# layout.net
KiCad netlist of a schematic drawn in EAGLE
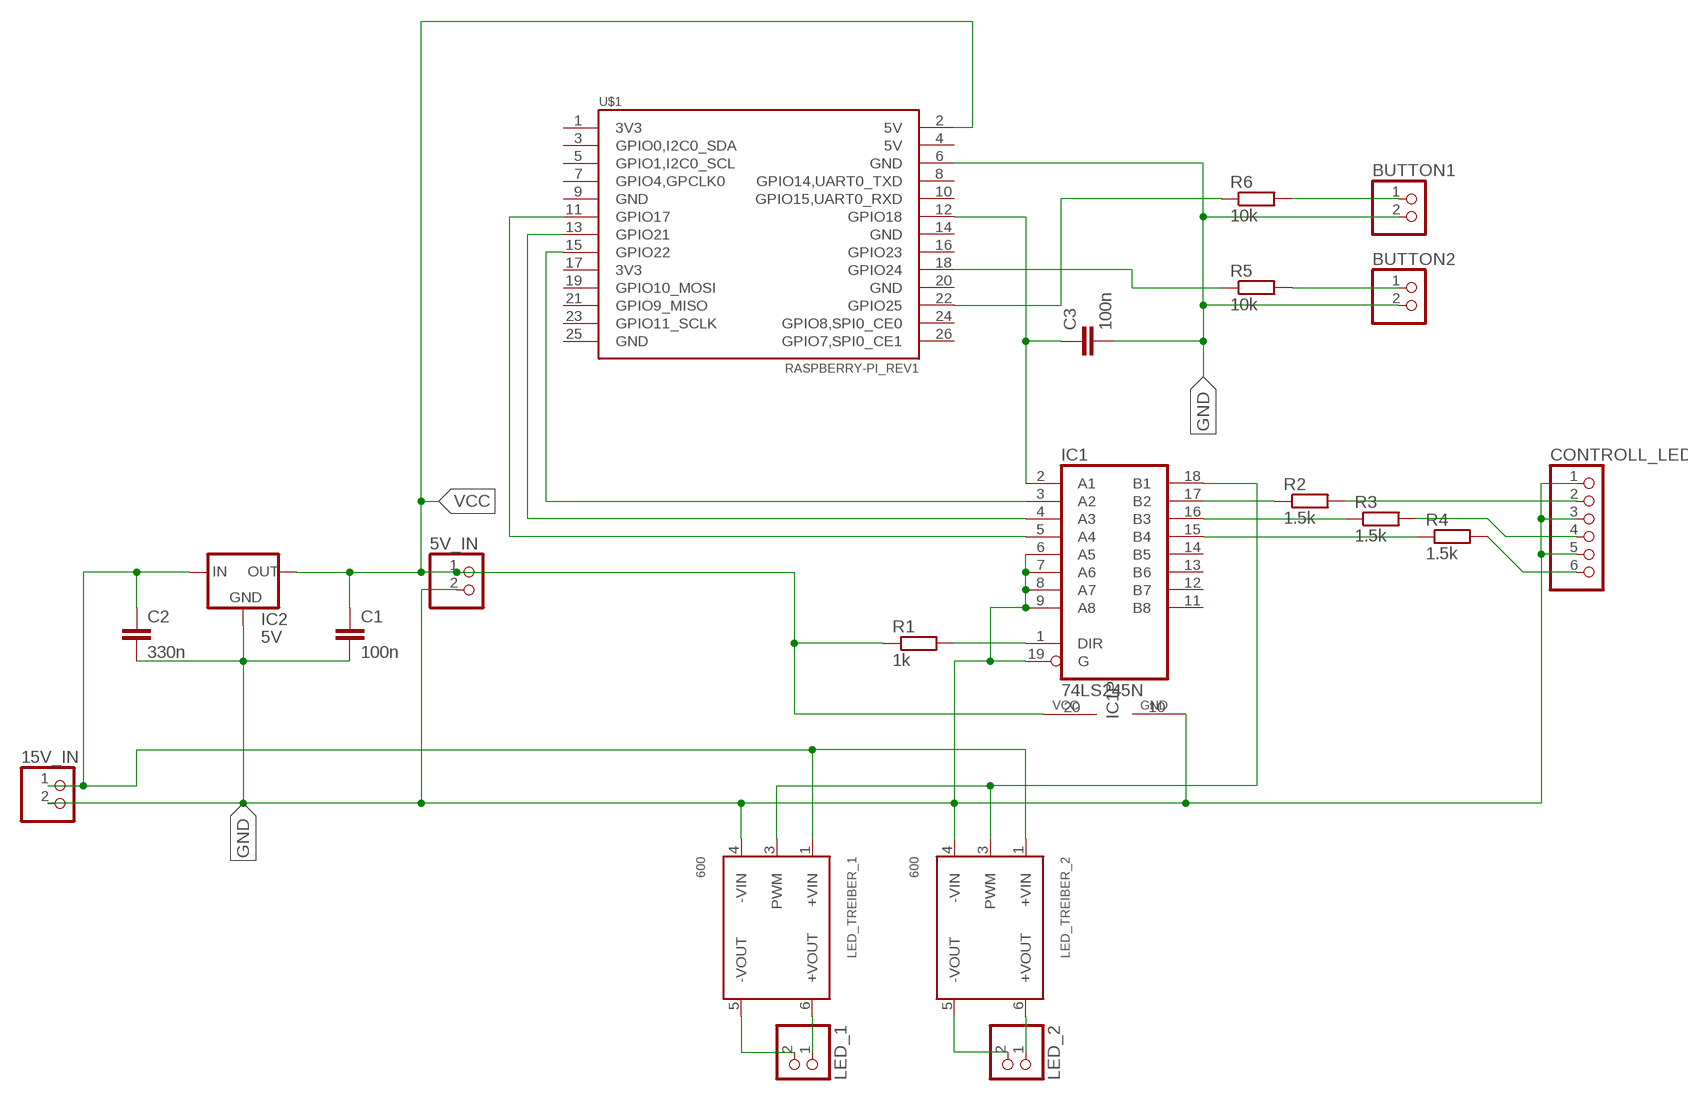
[diagram p0: schematic, sheet 1]

(export (version "E")
  (design (tool "Eeschema 10.0.6"))
  (components
    (comp (ref "5V_IN")
      (value "PINHD-1X2")
      (footprint "eagle-import:1X02")
      (libsource (lib "eagle-import") (part "PINHD-1X2"))
    )
    (comp (ref "15V_IN")
      (value "PINHD-1X2")
      (footprint "eagle-import:1X02")
      (libsource (lib "eagle-import") (part "PINHD-1X2"))
    )
    (comp (ref "BUTTON1")
      (value "PINHD-1X2")
      (footprint "eagle-import:1X02")
      (libsource (lib "eagle-import") (part "PINHD-1X2"))
    )
    (comp (ref "BUTTON2")
      (value "PINHD-1X2")
      (footprint "eagle-import:1X02")
      (libsource (lib "eagle-import") (part "PINHD-1X2"))
    )
    (comp (ref "C1")
      (value "100n")
      (footprint "eagle-import:C7.5B3")
      (libsource (lib "eagle-import") (part "C7.5/3"))
    )
    (comp (ref "C2")
      (value "330n")
      (footprint "eagle-import:C7.5B5")
      (libsource (lib "eagle-import") (part "C7.5/5"))
    )
    (comp (ref "C3")
      (value "100n")
      (footprint "eagle-import:C7.5B3")
      (libsource (lib "eagle-import") (part "C7.5/3"))
    )
    (comp (ref "CONTROLL_LED")
      (value "PINHD-1X6")
      (footprint "eagle-import:1X06")
      (libsource (lib "eagle-import") (part "PINHD-1X6"))
    )
    (comp (ref "IC1")
      (value "74LS245N")
      (footprint "eagle-import:DIL20")
      (libsource (lib "eagle-import") (part "74245NLS"))
    )
    (comp (ref "IC2")
      (value "5V")
      (footprint "eagle-import:78XXS")
      (libsource (lib "eagle-import") (part "78XXS"))
    )
    (comp (ref "LED_1")
      (value "PINHD-1X2")
      (footprint "eagle-import:1X02")
      (libsource (lib "eagle-import") (part "PINHD-1X2"))
    )
    (comp (ref "LED_2")
      (value "PINHD-1X2")
      (footprint "eagle-import:1X02")
      (libsource (lib "eagle-import") (part "PINHD-1X2"))
    )
    (comp (ref "LED_TREIBER_1")
      (value "600")
      (footprint "eagle-import:LDD-L1")
      (libsource (lib "eagle-import") (part "LDD-L1"))
    )
    (comp (ref "LED_TREIBER_2")
      (value "600")
      (footprint "eagle-import:LDD-L1")
      (libsource (lib "eagle-import") (part "LDD-L1"))
    )
    (comp (ref "R1")
      (value "1k")
      (footprint "eagle-import:0309_10")
      (libsource (lib "eagle-import") (part "R-EU_0309/10"))
    )
    (comp (ref "R2")
      (value "1.5k")
      (footprint "eagle-import:0309_10")
      (libsource (lib "eagle-import") (part "R-EU_0309/10"))
    )
    (comp (ref "R3")
      (value "1.5k")
      (footprint "eagle-import:0309_10")
      (libsource (lib "eagle-import") (part "R-EU_0309/10"))
    )
    (comp (ref "R4")
      (value "1.5k")
      (footprint "eagle-import:0309_10")
      (libsource (lib "eagle-import") (part "R-EU_0309/10"))
    )
    (comp (ref "R5")
      (value "10k")
      (footprint "eagle-import:0309_10")
      (libsource (lib "eagle-import") (part "R-EU_0309/10"))
    )
    (comp (ref "R6")
      (value "10k")
      (footprint "eagle-import:0309_10")
      (libsource (lib "eagle-import") (part "R-EU_0309/10"))
    )
    (comp (ref "U$1")
      (value "RASPBERRY-PI_REV1")
      (footprint "eagle-import:RASPBERRY-PI_REV1")
      (libsource (lib "eagle-import") (part "RASPBERRY-PI_REV1"))
    )
  )
  (nets
    (net (code "1") (name "GND") (class "Default")
      (node (ref "15V_IN") (pin "2") (pinfunction "2_2") (pintype "passive"))
      (node (ref "5V_IN") (pin "2") (pinfunction "2_2") (pintype "passive"))
      (node (ref "BUTTON1") (pin "2") (pinfunction "2_2") (pintype "passive"))
      (node (ref "BUTTON2") (pin "2") (pinfunction "2_2") (pintype "passive"))
      (node (ref "C1") (pin "2") (pinfunction "2_2") (pintype "passive"))
      (node (ref "C2") (pin "2") (pinfunction "2_2") (pintype "passive"))
      (node (ref "C3") (pin "2") (pinfunction "2_2") (pintype "passive"))
      (node (ref "CONTROLL_LED") (pin "1") (pinfunction "1_1") (pintype "passive"))
      (node (ref "CONTROLL_LED") (pin "3") (pinfunction "3_3") (pintype "passive"))
      (node (ref "CONTROLL_LED") (pin "5") (pinfunction "5_5") (pintype "passive"))
      (node (ref "IC1") (pin "10") (pinfunction "GND_10") (pintype "power_in"))
      (node (ref "IC1") (pin "19") (pinfunction "G_19") (pintype "input"))
      (node (ref "IC1") (pin "6") (pinfunction "A5_6") (pintype "bidirectional"))
      (node (ref "IC1") (pin "7") (pinfunction "A6_7") (pintype "bidirectional"))
      (node (ref "IC1") (pin "8") (pinfunction "A7_8") (pintype "bidirectional"))
      (node (ref "IC1") (pin "9") (pinfunction "A8_9") (pintype "bidirectional"))
      (node (ref "IC2") (pin "GND") (pinfunction "GND_GND") (pintype "input"))
      (node (ref "LED_TREIBER_1") (pin "4") (pinfunction "-VIN_4") (pintype "input"))
      (node (ref "LED_TREIBER_2") (pin "4") (pinfunction "-VIN_4") (pintype "input"))
      (node (ref "U$1") (pin "6") (pinfunction "GND_6") (pintype "bidirectional"))
    )
    (net (code "2") (name "Net-(BUTTON1-Pad1)") (class "Default")
      (node (ref "BUTTON1") (pin "1") (pinfunction "1_1") (pintype "passive"))
      (node (ref "R6") (pin "2") (pinfunction "2_2") (pintype "passive"))
    )
    (net (code "3") (name "Net-(BUTTON2-Pad1)") (class "Default")
      (node (ref "BUTTON2") (pin "1") (pinfunction "1_1") (pintype "passive"))
      (node (ref "R5") (pin "2") (pinfunction "2_2") (pintype "passive"))
    )
    (net (code "4") (name "Net-(CONTROLL_LED-Pad2)") (class "Default")
      (node (ref "CONTROLL_LED") (pin "2") (pinfunction "2_2") (pintype "passive"))
      (node (ref "R2") (pin "2") (pinfunction "2_2") (pintype "passive"))
    )
    (net (code "5") (name "Net-(CONTROLL_LED-Pad4)") (class "Default")
      (node (ref "CONTROLL_LED") (pin "4") (pinfunction "4_4") (pintype "passive"))
      (node (ref "R3") (pin "2") (pinfunction "2_2") (pintype "passive"))
    )
    (net (code "6") (name "Net-(CONTROLL_LED-Pad6)") (class "Default")
      (node (ref "CONTROLL_LED") (pin "6") (pinfunction "6_6") (pintype "passive"))
      (node (ref "R4") (pin "2") (pinfunction "2_2") (pintype "passive"))
    )
    (net (code "7") (name "Net-(IC1A-A1)") (class "Default")
      (node (ref "C3") (pin "1") (pinfunction "1_1") (pintype "passive"))
      (node (ref "IC1") (pin "2") (pinfunction "A1_2") (pintype "bidirectional"))
      (node (ref "U$1") (pin "12") (pinfunction "GPIO18_12") (pintype "bidirectional"))
    )
    (net (code "8") (name "Net-(IC1A-A2)") (class "Default")
      (node (ref "IC1") (pin "3") (pinfunction "A2_3") (pintype "bidirectional"))
      (node (ref "U$1") (pin "15") (pinfunction "GPIO22_15") (pintype "bidirectional"))
    )
    (net (code "9") (name "Net-(IC1A-A3)") (class "Default")
      (node (ref "IC1") (pin "4") (pinfunction "A3_4") (pintype "bidirectional"))
      (node (ref "U$1") (pin "13") (pinfunction "GPIO21_13") (pintype "bidirectional"))
    )
    (net (code "10") (name "Net-(IC1A-A4)") (class "Default")
      (node (ref "IC1") (pin "5") (pinfunction "A4_5") (pintype "bidirectional"))
      (node (ref "U$1") (pin "11") (pinfunction "GPIO17_11") (pintype "bidirectional"))
    )
    (net (code "11") (name "Net-(IC1A-B1)") (class "Default")
      (node (ref "IC1") (pin "18") (pinfunction "B1_18") (pintype "bidirectional"))
      (node (ref "LED_TREIBER_1") (pin "3") (pinfunction "PWM_3") (pintype "input"))
      (node (ref "LED_TREIBER_2") (pin "3") (pinfunction "PWM_3") (pintype "input"))
    )
    (net (code "12") (name "Net-(IC1A-B2)") (class "Default")
      (node (ref "IC1") (pin "17") (pinfunction "B2_17") (pintype "bidirectional"))
      (node (ref "R2") (pin "1") (pinfunction "1_1") (pintype "passive"))
    )
    (net (code "13") (name "Net-(IC1A-B3)") (class "Default")
      (node (ref "IC1") (pin "16") (pinfunction "B3_16") (pintype "bidirectional"))
      (node (ref "R3") (pin "1") (pinfunction "1_1") (pintype "passive"))
    )
    (net (code "14") (name "Net-(IC1A-B4)") (class "Default")
      (node (ref "IC1") (pin "15") (pinfunction "B4_15") (pintype "bidirectional"))
      (node (ref "R4") (pin "1") (pinfunction "1_1") (pintype "passive"))
    )
    (net (code "15") (name "Net-(IC1A-DIR)") (class "Default")
      (node (ref "IC1") (pin "1") (pinfunction "DIR_1") (pintype "input"))
      (node (ref "R1") (pin "2") (pinfunction "2_2") (pintype "passive"))
    )
    (net (code "16") (name "Net-(LED_TREIBER_1-+VIN)") (class "Default")
      (node (ref "15V_IN") (pin "1") (pinfunction "1_1") (pintype "passive"))
      (node (ref "C2") (pin "1") (pinfunction "1_1") (pintype "passive"))
      (node (ref "IC2") (pin "IN") (pinfunction "IN_IN") (pintype "input"))
      (node (ref "LED_TREIBER_1") (pin "1") (pinfunction "+VIN_1") (pintype "input"))
      (node (ref "LED_TREIBER_2") (pin "1") (pinfunction "+VIN_1") (pintype "input"))
    )
    (net (code "17") (name "Net-(LED_TREIBER_1-+VOUT)") (class "Default")
      (node (ref "LED_1") (pin "1") (pinfunction "1_1") (pintype "passive"))
      (node (ref "LED_TREIBER_1") (pin "6") (pinfunction "+VOUT_6") (pintype "output"))
    )
    (net (code "18") (name "Net-(LED_TREIBER_1--VOUT)") (class "Default")
      (node (ref "LED_1") (pin "2") (pinfunction "2_2") (pintype "passive"))
      (node (ref "LED_TREIBER_1") (pin "5") (pinfunction "-VOUT_5") (pintype "output"))
    )
    (net (code "19") (name "Net-(LED_TREIBER_2-+VOUT)") (class "Default")
      (node (ref "LED_2") (pin "1") (pinfunction "1_1") (pintype "passive"))
      (node (ref "LED_TREIBER_2") (pin "6") (pinfunction "+VOUT_6") (pintype "output"))
    )
    (net (code "20") (name "Net-(LED_TREIBER_2--VOUT)") (class "Default")
      (node (ref "LED_2") (pin "2") (pinfunction "2_2") (pintype "passive"))
      (node (ref "LED_TREIBER_2") (pin "5") (pinfunction "-VOUT_5") (pintype "output"))
    )
    (net (code "21") (name "Net-(U$1-GPIO24)") (class "Default")
      (node (ref "R5") (pin "1") (pinfunction "1_1") (pintype "passive"))
      (node (ref "U$1") (pin "18") (pinfunction "GPIO24_18") (pintype "bidirectional"))
    )
    (net (code "22") (name "Net-(U$1-GPIO25)") (class "Default")
      (node (ref "R6") (pin "1") (pinfunction "1_1") (pintype "passive"))
      (node (ref "U$1") (pin "22") (pinfunction "GPIO25_22") (pintype "bidirectional"))
    )
    (net (code "23") (name "VCC") (class "Default")
      (node (ref "5V_IN") (pin "1") (pinfunction "1_1") (pintype "passive"))
      (node (ref "C1") (pin "1") (pinfunction "1_1") (pintype "passive"))
      (node (ref "IC1") (pin "20") (pinfunction "VCC_20") (pintype "power_in"))
      (node (ref "IC2") (pin "OUT") (pinfunction "OUT_OUT") (pintype "passive"))
      (node (ref "R1") (pin "1") (pinfunction "1_1") (pintype "passive"))
      (node (ref "U$1") (pin "2") (pinfunction "5V_2") (pintype "bidirectional"))
    )
    (net (code "24") (name "unconnected-(IC1A-B5-Pad14)") (class "Default")
      (node (ref "IC1") (pin "14") (pinfunction "B5_14") (pintype "bidirectional"))
    )
    (net (code "25") (name "unconnected-(IC1A-B6-Pad13)") (class "Default")
      (node (ref "IC1") (pin "13") (pinfunction "B6_13") (pintype "bidirectional"))
    )
    (net (code "26") (name "unconnected-(IC1A-B7-Pad12)") (class "Default")
      (node (ref "IC1") (pin "12") (pinfunction "B7_12") (pintype "bidirectional"))
    )
    (net (code "27") (name "unconnected-(IC1A-B8-Pad11)") (class "Default")
      (node (ref "IC1") (pin "11") (pinfunction "B8_11") (pintype "bidirectional"))
    )
    (net (code "28") (name "unconnected-(U$1-3V3-Pad1)") (class "Default")
      (node (ref "U$1") (pin "1") (pinfunction "3V3_1") (pintype "bidirectional"))
    )
    (net (code "29") (name "unconnected-(U$1-3V3-Pad17)") (class "Default")
      (node (ref "U$1") (pin "17") (pinfunction "3V3_17") (pintype "bidirectional"))
    )
    (net (code "30") (name "unconnected-(U$1-5V-Pad4)") (class "Default")
      (node (ref "U$1") (pin "4") (pinfunction "5V_4") (pintype "bidirectional"))
    )
    (net (code "31") (name "unconnected-(U$1-GND-Pad9)") (class "Default")
      (node (ref "U$1") (pin "9") (pinfunction "GND_9") (pintype "bidirectional"))
    )
    (net (code "32") (name "unconnected-(U$1-GND-Pad14)") (class "Default")
      (node (ref "U$1") (pin "14") (pinfunction "GND_14") (pintype "bidirectional"))
    )
    (net (code "33") (name "unconnected-(U$1-GND-Pad20)") (class "Default")
      (node (ref "U$1") (pin "20") (pinfunction "GND_20") (pintype "bidirectional"))
    )
    (net (code "34") (name "unconnected-(U$1-GND-Pad25)") (class "Default")
      (node (ref "U$1") (pin "25") (pinfunction "GND_25") (pintype "bidirectional"))
    )
    (net (code "35") (name "unconnected-(U$1-GPIO0,I2C0_SDA-Pad3)") (class "Default")
      (node (ref "U$1") (pin "3") (pinfunction "GPIO0,I2C0_SDA_3") (pintype "bidirectional"))
    )
    (net (code "36") (name "unconnected-(U$1-GPIO1,I2C0_SCL-Pad5)") (class "Default")
      (node (ref "U$1") (pin "5") (pinfunction "GPIO1,I2C0_SCL_5") (pintype "bidirectional"))
    )
    (net (code "37") (name "unconnected-(U$1-GPIO4,GPCLK0-Pad7)") (class "Default")
      (node (ref "U$1") (pin "7") (pinfunction "GPIO4,GPCLK0_7") (pintype "bidirectional"))
    )
    (net (code "38") (name "unconnected-(U$1-GPIO7,SPI0_CE1-Pad26)") (class "Default")
      (node (ref "U$1") (pin "26") (pinfunction "GPIO7,SPI0_CE1_26") (pintype "bidirectional"))
    )
    (net (code "39") (name "unconnected-(U$1-GPIO8,SPI0_CE0-Pad24)") (class "Default")
      (node (ref "U$1") (pin "24") (pinfunction "GPIO8,SPI0_CE0_24") (pintype "bidirectional"))
    )
    (net (code "40") (name "unconnected-(U$1-GPIO9_MISO-Pad21)") (class "Default")
      (node (ref "U$1") (pin "21") (pinfunction "GPIO9_MISO_21") (pintype "bidirectional"))
    )
    (net (code "41") (name "unconnected-(U$1-GPIO10_MOSI-Pad19)") (class "Default")
      (node (ref "U$1") (pin "19") (pinfunction "GPIO10_MOSI_19") (pintype "bidirectional"))
    )
    (net (code "42") (name "unconnected-(U$1-GPIO11_SCLK-Pad23)") (class "Default")
      (node (ref "U$1") (pin "23") (pinfunction "GPIO11_SCLK_23") (pintype "bidirectional"))
    )
    (net (code "43") (name "unconnected-(U$1-GPIO14,UART0_TXD-Pad8)") (class "Default")
      (node (ref "U$1") (pin "8") (pinfunction "GPIO14,UART0_TXD_8") (pintype "bidirectional"))
    )
    (net (code "44") (name "unconnected-(U$1-GPIO15,UART0_RXD-Pad10)") (class "Default")
      (node (ref "U$1") (pin "10") (pinfunction "GPIO15,UART0_RXD_10") (pintype "bidirectional"))
    )
    (net (code "45") (name "unconnected-(U$1-GPIO23-Pad16)") (class "Default")
      (node (ref "U$1") (pin "16") (pinfunction "GPIO23_16") (pintype "bidirectional"))
    )
  )
)
